# ISP_medium_main.net
KiCad netlist of a schematic drawn in Altium Designer
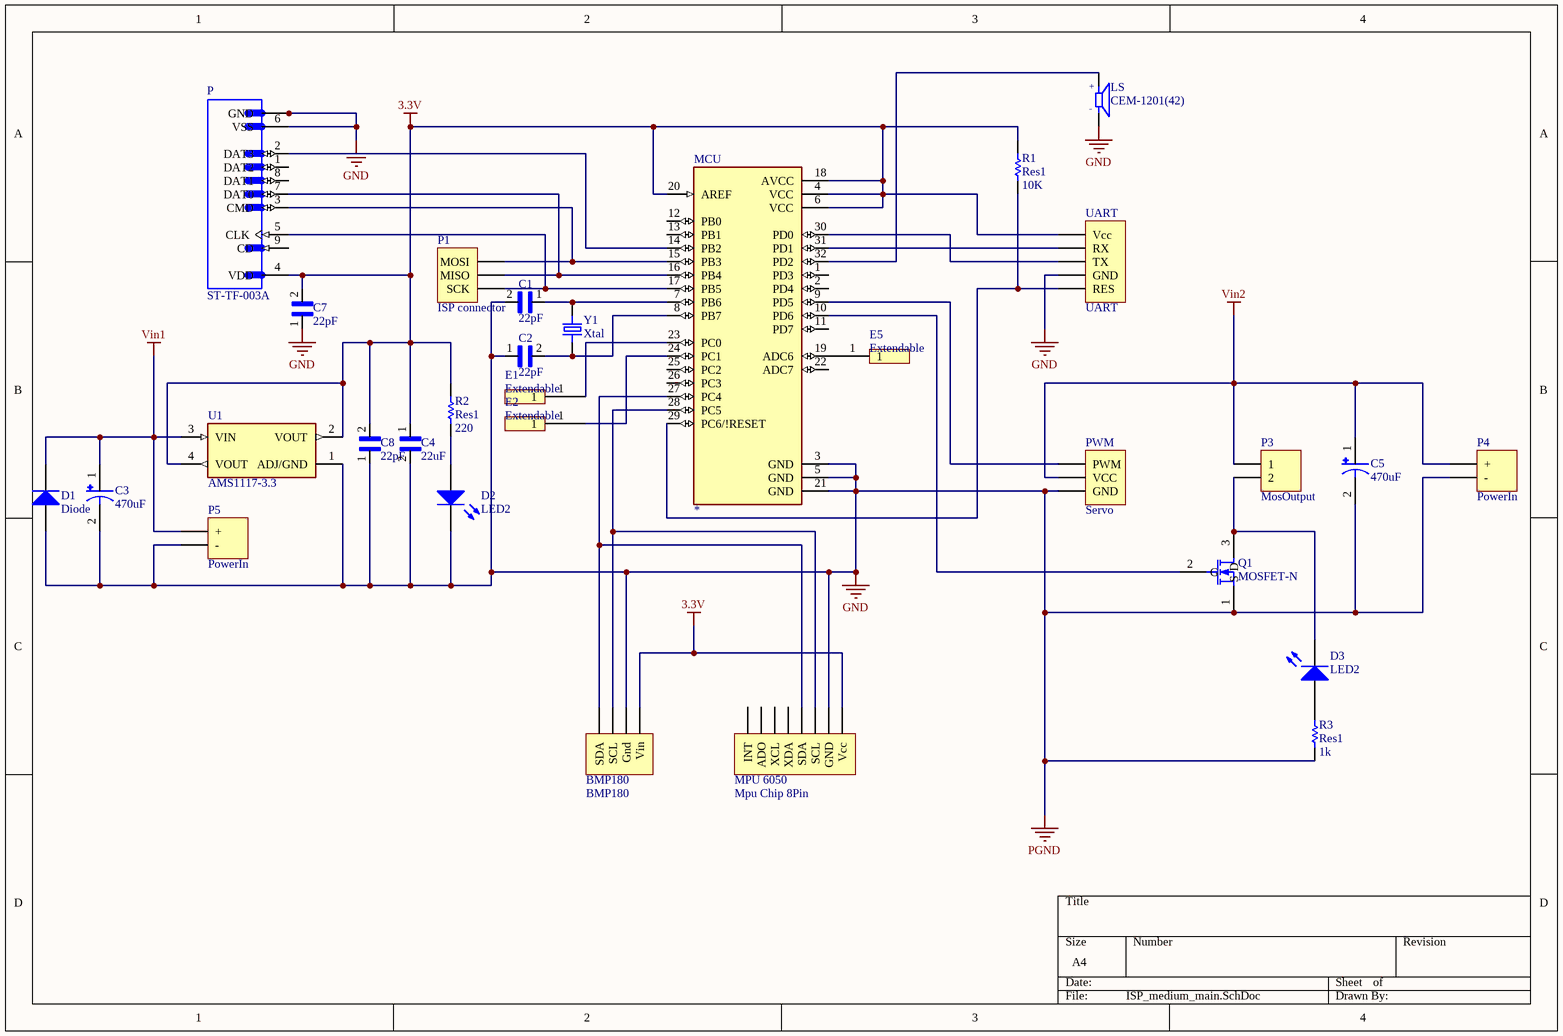
[diagram p0: ISP_medium_main.SchDoc]

(export (version "E")
  (design (tool "Eeschema 10.0.6"))
  (components
    (comp (ref "BMP180")
      (value "BMP180")
      (footprint "ISP_medium_pcb:BMP280")
      (description "Chip Connector 4 Pin for BMP180")
      (fields (field (name "PUBLISHER") "Altium Limited"))
      (libsource (lib "ISP_medium_sch") (part "BMP180"))
    )
    (comp (ref "C1")
      (value "22pF")
      (footprint "CAP1602")
      (description "SMD Capacitor X6S(EIA) with Capacitance: 22pF")
      (fields (field (name "MF") "Murata") (field (name "MP") "GRM319C81C106MA12J"))
      (libsource (lib "") (part "22pF_1"))
    )
    (comp (ref "C2")
      (value "22pF")
      (footprint "CAP1602")
      (description "SMD Capacitor X6S(EIA) with Capacitance: 22pF")
      (fields (field (name "MF") "Murata") (field (name "MP") "GRM319C81C106MA12J"))
      (libsource (lib "") (part "22pF_2"))
    )
    (comp (ref "C3")
      (value "470uF")
      (footprint "CAPAE7066X77M")
      (description "470µF 16V Aluminum Electrolytic Capacitors Radial")
      (fields (field (name "MF") "Panasonic") (field (name "MP") "EEE-FC1C471AP"))
      (libsource (lib "ISP_medium_sch") (part "470uF"))
    )
    (comp (ref "C4")
      (value "22uF")
      (footprint "CAP1602")
      (description "SMD Capacitor X6S(EIA) with Capacitance: 22pF")
      (fields (field (name "MF") "Murata") (field (name "MP") "GRM319C81C106MA12J"))
      (libsource (lib "ISP_medium_sch") (part "100nF"))
    )
    (comp (ref "C5")
      (value "470uF")
      (footprint "CAPAE7066X77M")
      (description "470µF 16V Aluminum Electrolytic Capacitors Radial")
      (fields (field (name "MF") "Panasonic") (field (name "MP") "EEE-FC1C471AP"))
      (libsource (lib "ISP_medium_sch") (part "470uF"))
    )
    (comp (ref "C7")
      (value "22pF")
      (footprint "CAP1602")
      (description "SMD Capacitor X6S(EIA) with Capacitance: 22pF")
      (fields (field (name "MF") "Murata") (field (name "MP") "GRM319C81C106MA12J"))
      (libsource (lib "ISP_medium_sch") (part "22pF"))
    )
    (comp (ref "C8")
      (value "22pF")
      (footprint "CAP1602")
      (description "SMD Capacitor X6S(EIA) with Capacitance: 22pF")
      (fields (field (name "MF") "Murata") (field (name "MP") "GRM319C81C106MA12J"))
      (libsource (lib "ISP_medium_sch") (part "22pF"))
    )
    (comp (ref "D1")
      (value "Diode")
      (footprint "DIOM4227X24N")
      (description "Default Diode")
      (fields (field (name "PUBLISHER") "Altium Limited"))
      (libsource (lib "ISP_medium_sch") (part "Diode"))
    )
    (comp (ref "D2")
      (value "LED2")
      (footprint "3.2X1.6X1.1")
      (description "Typical RED, GREEN, YELLOW, AMBER GaAs LED")
      (fields (field (name "PUBLISHER") "Altium Limited"))
      (libsource (lib "Miscellaneous Devices") (part "LED2"))
    )
    (comp (ref "D3")
      (value "LED2")
      (footprint "3.2X1.6X1.1")
      (description "Typical RED, GREEN, YELLOW, AMBER GaAs LED")
      (fields (field (name "PUBLISHER") "Altium Limited"))
      (libsource (lib "Miscellaneous Devices") (part "LED2"))
    )
    (comp (ref "E1")
      (value "Extendable")
      (footprint "Extendable")
      (libsource (lib "ISP_medium_sch") (part "Extendable"))
    )
    (comp (ref "E2")
      (value "Extendable")
      (footprint "Extendable")
      (libsource (lib "ISP_medium_sch") (part "Extendable"))
    )
    (comp (ref "E5") (value "Extendable") (footprint "Extendable") (libsource (lib "") (part "Extendable_1")))
    (comp (ref "LS")
      (value "CEM-1201(42)")
      (footprint "CUI_CEM-1201(42)")
      (description "12 mm, 1,5 V, 85 dB, furo passante, campainha el茅trica transdutora de 谩udio magn茅tica")
      (fields (field (name "MF") "CUI Devices") (field (name "MP") "CEM-1201_42_"))
      (libsource (lib "Buzzer-1201_42_") (part "CEM-1201(42)"))
    )
    (comp (ref "MCU")
      (value "*")
      (footprint "QFP80P900X900X120-32N")
      (description "AVR AVRÂ® ATmega Microcontroller IC 8-Bit 20MHz 32KB _16K x 16_ FLASH 32-TQFP _7x7_")
      (fields (field (name "MP") "ATMEGA328P-AU") (field (name "MF") "Microchip Technology"))
      (libsource (lib "ATMEGA328P-AU") (part "ATMEGA328P-AU"))
    )
    (comp (ref "MPU 6050")
      (value "Mpu Chip 8Pin")
      (footprint "Mpu 8Pin")
      (description "Chip Mpu 8Pin")
      (fields (field (name "PUBLISHER") "Altium Limited"))
      (libsource (lib "ISP_medium_sch") (part "Chip Mpu 8Pin"))
    )
    (comp (ref "P")
      (value "ST-TF-003A")
      (footprint "MicroSD")
      (description "Micro SD Card Socket")
      (fields (field (name "MF") "Suntech"))
      (libsource (lib "ISP_medium_sch") (part "ST-TF-003A"))
    )
    (comp (ref "P1")
      (value "ISP connector")
      (footprint "ISP connector")
      (description "Header, 3-Pin")
      (fields (field (name "PUBLISHER") "Altium Limited"))
      (libsource (lib "ISP_medium_sch") (part "ISP connector"))
    )
    (comp (ref "P3")
      (value "MosOutput")
      (footprint "KF126-2P-Connector")
      (description "Header, 2-Pin")
      (fields (field (name "PUBLISHER") "Altium Limited"))
      (libsource (lib "ISP_medium_sch") (part "MosOutput"))
    )
    (comp (ref "P4")
      (value "PowerIn")
      (footprint "PowerIn")
      (description "Header, 2-Pin")
      (fields (field (name "PUBLISHER") "Altium Limited"))
      (libsource (lib "ISP_medium_sch") (part "PowerIn"))
    )
    (comp (ref "P5")
      (value "PowerIn")
      (footprint "PowerIn")
      (description "Header, 2-Pin")
      (fields (field (name "PUBLISHER") "Altium Limited"))
      (libsource (lib "ISP_medium_sch") (part "PowerIn"))
    )
    (comp (ref "PWM")
      (value "Servo")
      (footprint "Servo")
      (description "Header, 3-Pin")
      (fields (field (name "PUBLISHER") "Altium Limited"))
      (libsource (lib "ISP_medium_sch") (part "Servo"))
    )
    (comp (ref "Q1")
      (value "MOSFET-N")
      (footprint "SOT23-3")
      (description "N-Channel MOSFET")
      (fields (field (name "PUBLISHER") "Altium Limited"))
      (libsource (lib "ISP_medium_sch") (part "MOSFET-N"))
    )
    (comp (ref "R1")
      (value "Res1")
      (footprint "RES 1602")
      (description "Resistor")
      (fields (field (name "ALTIUM_VALUE") "10K") (field (name "PUBLISHER") "Altium Limited"))
      (libsource (lib "ISP_medium_sch") (part "Res1"))
    )
    (comp (ref "R2")
      (value "Res1")
      (footprint "RES 1602")
      (description "Resistor")
      (fields (field (name "ALTIUM_VALUE") "220") (field (name "PUBLISHER") "Altium Limited"))
      (libsource (lib "ISP_medium_sch") (part "Res1"))
    )
    (comp (ref "R3")
      (value "Res1")
      (footprint "RES 1602")
      (description "Resistor")
      (fields (field (name "ALTIUM_VALUE") "1k") (field (name "PUBLISHER") "Altium Limited"))
      (libsource (lib "ISP_medium_sch") (part "Res1"))
    )
    (comp (ref "U1")
      (value "AMS1117-3.3")
      (footprint "SOT230P700X180-4N")
      (description "Sot223/Pkg 1-Amp 3.3-Volt Low Drop Out Voltage Regulatator")
      (fields (field (name "MF") "Advanced Monolithic Systems"))
      (libsource (lib "ISP_medium_sch") (part "AMS1117-3.3"))
    )
    (comp (ref "UART")
      (value "UART")
      (footprint "UART")
      (description "Header, 5-Pin, UART, for uploading")
      (fields (field (name "PUBLISHER") "Altium Limited"))
      (libsource (lib "ISP_medium_sch") (part "UART"))
    )
    (comp (ref "Y1")
      (value "Xtal")
      (footprint "XTAL")
      (fields (field (name "MP") "ECS-122.8-18-5PXEN-TR") (field (name "MF") "ECS Inc."))
      (libsource (lib "ISP_medium_sch") (part "Xtal"))
    )
  )
  (nets
    (net (code "1") (name "3.3V") (class "Default")
      (node (ref "BMP180") (pin "1") (pinfunction "Vin_1") (pintype "passive"))
      (node (ref "C4") (pin "1") (pinfunction "1_1") (pintype "passive"))
      (node (ref "C7") (pin "2") (pinfunction "2_2") (pintype "passive"))
      (node (ref "C8") (pin "2") (pinfunction "2_2") (pintype "passive"))
      (node (ref "MCU") (pin "18") (pinfunction "AVCC_18") (pintype "power_in"))
      (node (ref "MCU") (pin "20") (pinfunction "AREF_20") (pintype "input"))
      (node (ref "MCU") (pin "4") (pinfunction "VCC_4") (pintype "power_in"))
      (node (ref "MCU") (pin "6") (pinfunction "VCC_6") (pintype "power_in"))
      (node (ref "MPU 6050") (pin "1") (pinfunction "Vcc_1") (pintype "passive"))
      (node (ref "P") (pin "4") (pinfunction "VDD_4") (pintype "power_in"))
      (node (ref "R1") (pin "2") (pinfunction "2_2") (pintype "passive"))
      (node (ref "R2") (pin "2") (pinfunction "2_2") (pintype "passive"))
      (node (ref "U1") (pin "2") (pinfunction "VOUT_2") (pintype "output"))
      (node (ref "U1") (pin "4") (pinfunction "VOUT_4") (pintype "output"))
      (node (ref "UART") (pin "1") (pinfunction "Vcc_1") (pintype "passive"))
    )
    (net (code "2") (name "GND") (class "Default")
      (node (ref "BMP180") (pin "2") (pinfunction "Gnd_2") (pintype "passive"))
      (node (ref "C1") (pin "2") (pinfunction "2_2") (pintype "passive"))
      (node (ref "C2") (pin "1") (pinfunction "1_1") (pintype "passive"))
      (node (ref "C3") (pin "2") (pinfunction "-_2") (pintype "passive"))
      (node (ref "C4") (pin "2") (pinfunction "2_2") (pintype "passive"))
      (node (ref "C5") (pin "2") (pinfunction "-_2") (pintype "passive"))
      (node (ref "C7") (pin "1") (pinfunction "1_1") (pintype "passive"))
      (node (ref "C8") (pin "1") (pinfunction "1_1") (pintype "passive"))
      (node (ref "D1") (pin "1") (pinfunction "A_1") (pintype "passive"))
      (node (ref "D2") (pin "2") (pinfunction "K_2") (pintype "passive"))
      (node (ref "LS") (pin "M") (pinfunction "M_M") (pintype "passive"))
      (node (ref "MCU") (pin "21") (pinfunction "GND_21") (pintype "power_in"))
      (node (ref "MCU") (pin "3") (pinfunction "GND_3") (pintype "power_in"))
      (node (ref "MCU") (pin "5") (pinfunction "GND_5") (pintype "power_in"))
      (node (ref "MPU 6050") (pin "2") (pinfunction "GND_2") (pintype "passive"))
      (node (ref "P") (pin "6") (pinfunction "VSS_6") (pintype "passive"))
      (node (ref "P") (pin "G1") (pinfunction "GND_G1") (pintype "passive"))
      (node (ref "P") (pin "G2") (pinfunction "GND_G2") (pintype "passive"))
      (node (ref "P") (pin "G3") (pinfunction "GND_G3") (pintype "passive"))
      (node (ref "P") (pin "G4") (pinfunction "GND_G4") (pintype "passive"))
      (node (ref "P4") (pin "2") (pinfunction "-_2") (pintype "passive"))
      (node (ref "P5") (pin "2") (pinfunction "-_2") (pintype "passive"))
      (node (ref "PWM") (pin "3") (pinfunction "GND_3") (pintype "passive"))
      (node (ref "Q1") (pin "1") (pinfunction "S_1") (pintype "passive"))
      (node (ref "R3") (pin "1") (pinfunction "1_1") (pintype "passive"))
      (node (ref "U1") (pin "1") (pinfunction "ADJ/GND_1") (pintype "power_in"))
      (node (ref "UART") (pin "4") (pinfunction "GND_4") (pintype "passive"))
    )
    (net (code "3") (name "Net-(BMP180-SCL)") (class "Default")
      (node (ref "BMP180") (pin "3") (pinfunction "SCL_3") (pintype "passive"))
      (node (ref "MCU") (pin "28") (pinfunction "PC5_28") (pintype "bidirectional"))
      (node (ref "MPU 6050") (pin "3") (pinfunction "SCL_3") (pintype "passive"))
    )
    (net (code "4") (name "Net-(BMP180-SDA)") (class "Default")
      (node (ref "BMP180") (pin "4") (pinfunction "SDA_4") (pintype "passive"))
      (node (ref "MCU") (pin "27") (pinfunction "PC4_27") (pintype "bidirectional"))
      (node (ref "MPU 6050") (pin "4") (pinfunction "SDA_4") (pintype "passive"))
    )
    (net (code "5") (name "Net-(D2-A)") (class "Default")
      (node (ref "D2") (pin "1") (pinfunction "A_1") (pintype "passive"))
      (node (ref "R2") (pin "1") (pinfunction "1_1") (pintype "passive"))
    )
    (net (code "6") (name "Net-(D3-A)") (class "Default")
      (node (ref "D3") (pin "1") (pinfunction "A_1") (pintype "passive"))
      (node (ref "R3") (pin "2") (pinfunction "2_2") (pintype "passive"))
    )
    (net (code "7") (name "Net-(D3-K)") (class "Default")
      (node (ref "D3") (pin "2") (pinfunction "K_2") (pintype "passive"))
      (node (ref "P3") (pin "2") (pinfunction "2_2") (pintype "passive"))
      (node (ref "Q1") (pin "3") (pinfunction "D_3") (pintype "passive"))
    )
    (net (code "8") (name "Net-(MCU-ADC6)") (class "Default")
      (node (ref "E5") (pin "1") (pinfunction "1_1") (pintype "passive"))
      (node (ref "MCU") (pin "19") (pinfunction "ADC6_19") (pintype "bidirectional"))
    )
    (net (code "9") (name "Net-(MCU-PB2)") (class "Default")
      (node (ref "MCU") (pin "14") (pinfunction "PB2_14") (pintype "bidirectional"))
      (node (ref "P") (pin "2") (pinfunction "DAT3_2") (pintype "bidirectional"))
    )
    (net (code "10") (name "Net-(MCU-PB3)") (class "Default")
      (node (ref "MCU") (pin "15") (pinfunction "PB3_15") (pintype "bidirectional"))
      (node (ref "P") (pin "3") (pinfunction "CMD_3") (pintype "bidirectional"))
      (node (ref "P1") (pin "3") (pinfunction "MOSI_3") (pintype "passive"))
    )
    (net (code "11") (name "Net-(MCU-PB4)") (class "Default")
      (node (ref "MCU") (pin "16") (pinfunction "PB4_16") (pintype "bidirectional"))
      (node (ref "P") (pin "7") (pinfunction "DAT0_7") (pintype "bidirectional"))
      (node (ref "P1") (pin "2") (pinfunction "MISO_2") (pintype "passive"))
    )
    (net (code "12") (name "Net-(MCU-PB5)") (class "Default")
      (node (ref "MCU") (pin "17") (pinfunction "PB5_17") (pintype "bidirectional"))
      (node (ref "P") (pin "5") (pinfunction "CLK_5") (pintype "input"))
      (node (ref "P1") (pin "1") (pinfunction "SCK_1") (pintype "passive"))
    )
    (net (code "13") (name "Net-(MCU-PB6)") (class "Default")
      (node (ref "C1") (pin "1") (pinfunction "1_1") (pintype "passive"))
      (node (ref "MCU") (pin "7") (pinfunction "PB6_7") (pintype "bidirectional"))
      (node (ref "Y1") (pin "2") (pinfunction "2_2") (pintype "passive"))
    )
    (net (code "14") (name "Net-(MCU-PB7)") (class "Default")
      (node (ref "C2") (pin "2") (pinfunction "2_2") (pintype "passive"))
      (node (ref "MCU") (pin "8") (pinfunction "PB7_8") (pintype "bidirectional"))
      (node (ref "Y1") (pin "1") (pinfunction "1_1") (pintype "passive"))
    )
    (net (code "15") (name "Net-(MCU-PC0)") (class "Default")
      (node (ref "E1") (pin "1") (pinfunction "1_1") (pintype "passive"))
      (node (ref "MCU") (pin "23") (pinfunction "PC0_23") (pintype "bidirectional"))
    )
    (net (code "16") (name "Net-(MCU-PC1)") (class "Default")
      (node (ref "E2") (pin "1") (pinfunction "1_1") (pintype "passive"))
      (node (ref "MCU") (pin "24") (pinfunction "PC1_24") (pintype "bidirectional"))
    )
    (net (code "17") (name "Net-(MCU-PC6{slash}!RESET)") (class "Default")
      (node (ref "MCU") (pin "29") (pinfunction "PC6/!RESET_29") (pintype "bidirectional"))
      (node (ref "R1") (pin "1") (pinfunction "1_1") (pintype "passive"))
      (node (ref "UART") (pin "5") (pinfunction "RES_5") (pintype "passive"))
    )
    (net (code "18") (name "Net-(MCU-PD0)") (class "Default")
      (node (ref "MCU") (pin "30") (pinfunction "PD0_30") (pintype "bidirectional"))
      (node (ref "UART") (pin "3") (pinfunction "TX_3") (pintype "passive"))
    )
    (net (code "19") (name "Net-(MCU-PD1)") (class "Default")
      (node (ref "MCU") (pin "31") (pinfunction "PD1_31") (pintype "bidirectional"))
      (node (ref "UART") (pin "2") (pinfunction "RX_2") (pintype "passive"))
    )
    (net (code "20") (name "Net-(MCU-PD2)") (class "Default")
      (node (ref "LS") (pin "P") (pinfunction "P_P") (pintype "passive"))
      (node (ref "MCU") (pin "32") (pinfunction "PD2_32") (pintype "bidirectional"))
    )
    (net (code "21") (name "Net-(MCU-PD5)") (class "Default")
      (node (ref "MCU") (pin "9") (pinfunction "PD5_9") (pintype "bidirectional"))
      (node (ref "PWM") (pin "1") (pinfunction "PWM_1") (pintype "passive"))
    )
    (net (code "22") (name "Net-(MCU-PD6)") (class "Default")
      (node (ref "MCU") (pin "10") (pinfunction "PD6_10") (pintype "bidirectional"))
      (node (ref "Q1") (pin "2") (pinfunction "G_2") (pintype "passive"))
    )
    (net (code "23") (name "Vin1") (class "Default")
      (node (ref "C3") (pin "1") (pinfunction "+_1") (pintype "passive"))
      (node (ref "D1") (pin "2") (pinfunction "K_2") (pintype "passive"))
      (node (ref "P5") (pin "1") (pinfunction "+_1") (pintype "passive"))
      (node (ref "U1") (pin "3") (pinfunction "VIN_3") (pintype "input"))
    )
    (net (code "24") (name "Vin2") (class "Default")
      (node (ref "C5") (pin "1") (pinfunction "+_1") (pintype "passive"))
      (node (ref "P3") (pin "1") (pinfunction "1_1") (pintype "passive"))
      (node (ref "P4") (pin "1") (pinfunction "+_1") (pintype "passive"))
      (node (ref "PWM") (pin "2") (pinfunction "VCC_2") (pintype "passive"))
    )
    (net (code "25") (name "unconnected-(MCU-ADC7-Pad22)") (class "Default")
      (node (ref "MCU") (pin "22") (pinfunction "ADC7_22") (pintype "bidirectional"))
    )
    (net (code "26") (name "unconnected-(MCU-PB0-Pad12)") (class "Default")
      (node (ref "MCU") (pin "12") (pinfunction "PB0_12") (pintype "bidirectional"))
    )
    (net (code "27") (name "unconnected-(MCU-PB1-Pad13)") (class "Default")
      (node (ref "MCU") (pin "13") (pinfunction "PB1_13") (pintype "bidirectional"))
    )
    (net (code "28") (name "unconnected-(MCU-PC2-Pad25)") (class "Default")
      (node (ref "MCU") (pin "25") (pinfunction "PC2_25") (pintype "bidirectional"))
    )
    (net (code "29") (name "unconnected-(MCU-PC3-Pad26)") (class "Default")
      (node (ref "MCU") (pin "26") (pinfunction "PC3_26") (pintype "bidirectional"))
    )
    (net (code "30") (name "unconnected-(MCU-PD3-Pad1)") (class "Default")
      (node (ref "MCU") (pin "1") (pinfunction "PD3_1") (pintype "bidirectional"))
    )
    (net (code "31") (name "unconnected-(MCU-PD4-Pad2)") (class "Default")
      (node (ref "MCU") (pin "2") (pinfunction "PD4_2") (pintype "bidirectional"))
    )
    (net (code "32") (name "unconnected-(MCU-PD7-Pad11)") (class "Default")
      (node (ref "MCU") (pin "11") (pinfunction "PD7_11") (pintype "bidirectional"))
    )
    (net (code "33") (name "unconnected-(MPU 6050-ADO-Pad7)") (class "Default")
      (node (ref "MPU 6050") (pin "7") (pinfunction "ADO_7") (pintype "passive"))
    )
    (net (code "34") (name "unconnected-(MPU 6050-INT-Pad8)") (class "Default")
      (node (ref "MPU 6050") (pin "8") (pinfunction "INT_8") (pintype "passive"))
    )
    (net (code "35") (name "unconnected-(MPU 6050-XCL-Pad6)") (class "Default")
      (node (ref "MPU 6050") (pin "6") (pinfunction "XCL_6") (pintype "passive"))
    )
    (net (code "36") (name "unconnected-(MPU 6050-XDA-Pad5)") (class "Default")
      (node (ref "MPU 6050") (pin "5") (pinfunction "XDA_5") (pintype "passive"))
    )
    (net (code "37") (name "unconnected-(P-CD-Pad9)") (class "Default")
      (node (ref "P") (pin "9") (pinfunction "CD_9") (pintype "input"))
    )
    (net (code "38") (name "unconnected-(P-DAT1-Pad8)") (class "Default")
      (node (ref "P") (pin "8") (pinfunction "DAT1_8") (pintype "bidirectional"))
    )
    (net (code "39") (name "unconnected-(P-DAT2-Pad1)") (class "Default")
      (node (ref "P") (pin "1") (pinfunction "DAT2_1") (pintype "bidirectional"))
    )
  )
)
